# ADC_board.net
KiCad netlist of a schematic drawn in Altium Designer
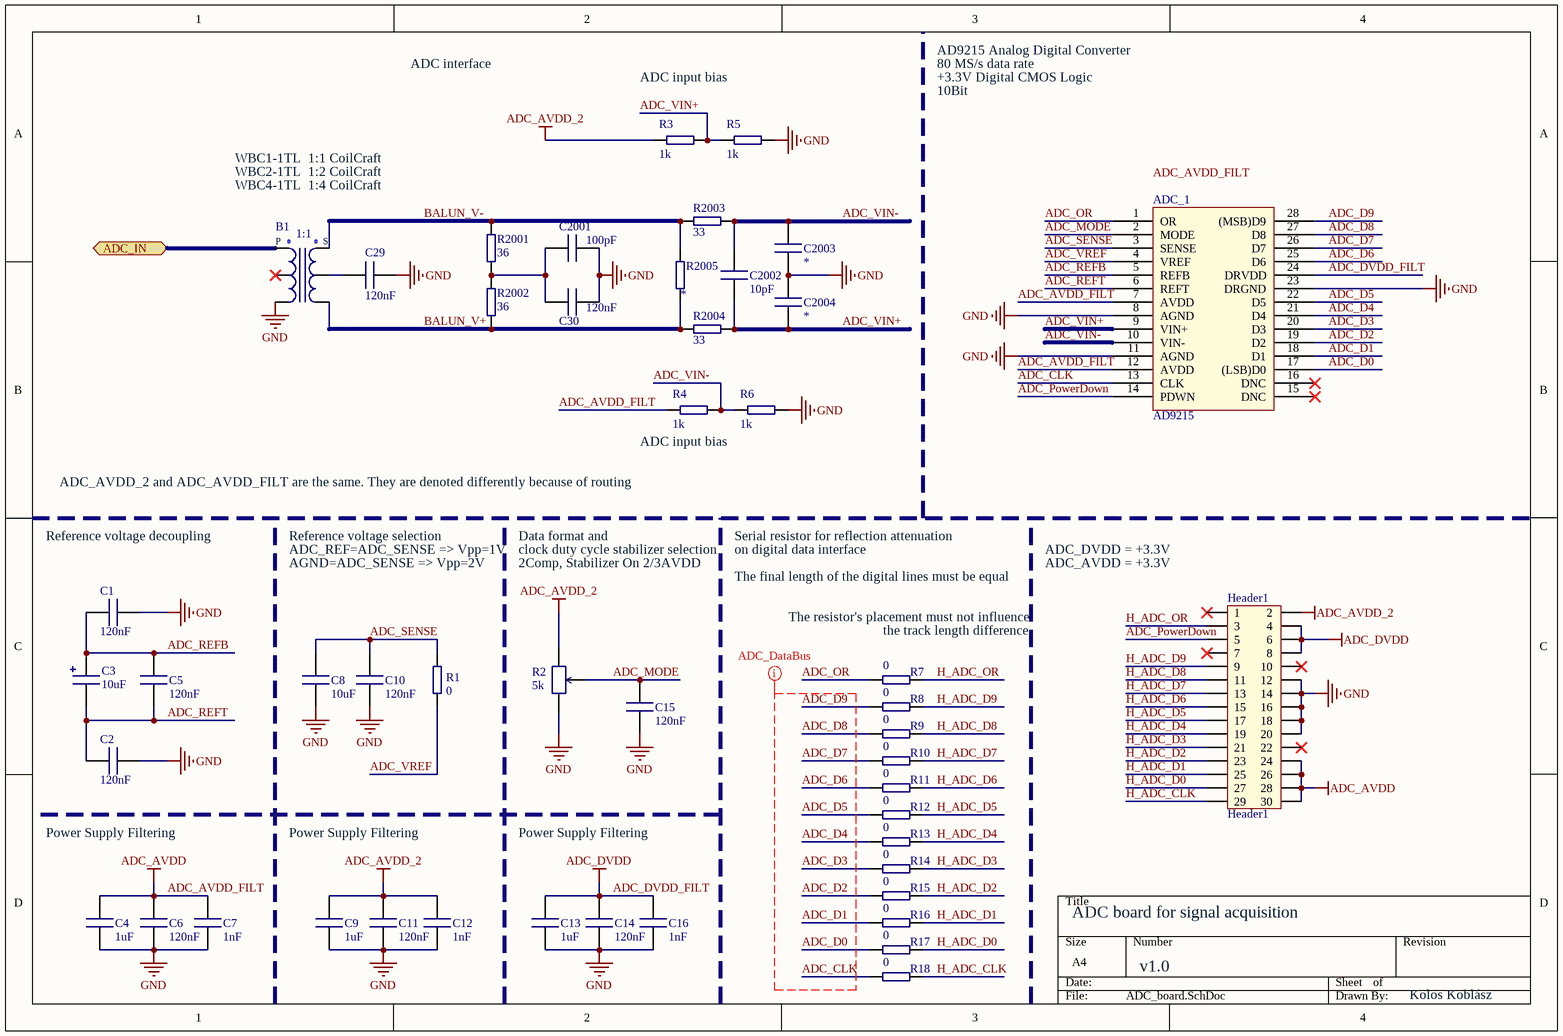
[diagram p0: ADC_board.SchDoc]

(export (version "E")
  (design (tool "Eeschema 10.0.6"))
  (components
    (comp (ref "ADC_1")
      (value "AD9215")
      (footprint "AD9215")
      (description "Analog Digital Converter")
      (fields (field (name "MANUFACTURER") "Analog Devices"))
      (libsource (lib "RadioProjectSchLib") (part "AD9215"))
    )
    (comp (ref "B1")
      (value "Balun")
      (footprint "Balun_Coil_Craft_WBC")
      (description "SMD Balun")
      (fields
        (field (name "IMPEDANCETRANSFORMATION P : S") "1:1")
        (field (name "MANUFACTURER") "CoilCraft")
        (field (name "PARTNUMBER") "WBC1-1TL")
      )
      (libsource (lib "RadioProjectSchLib") (part "Balun3"))
    )
    (comp (ref "C1")
      (value "120nF")
      (footprint "0805 SMD Passive")
      (description "SMD Capacitor")
      (fields (field (name "Comment") "Cap1"))
      (libsource (lib "RadioProjectSchLib") (part "Cap1"))
    )
    (comp (ref "C2")
      (value "120nF")
      (footprint "0805 SMD Passive")
      (description "SMD Capacitor")
      (fields (field (name "Comment") "Cap1"))
      (libsource (lib "RadioProjectSchLib") (part "Cap1"))
    )
    (comp (ref "C3")
      (value "10uF")
      (footprint "ELKO_CAP")
      (description "SMD Polarized Capacitor")
      (fields (field (name "Comment") "Cap2"))
      (libsource (lib "RadioProjectSchLib") (part "Cap2"))
    )
    (comp (ref "C4")
      (value "1uF")
      (footprint "0805 SMD Passive")
      (description "SMD Capacitor")
      (fields (field (name "Comment") "Cap1"))
      (libsource (lib "RadioProjectSchLib") (part "Cap1"))
    )
    (comp (ref "C5")
      (value "120nF")
      (footprint "0805 SMD Passive")
      (description "SMD Capacitor")
      (fields (field (name "Comment") "Cap1"))
      (libsource (lib "RadioProjectSchLib") (part "Cap1"))
    )
    (comp (ref "C6")
      (value "120nF")
      (footprint "0805 SMD Passive")
      (description "SMD Capacitor")
      (fields (field (name "Comment") "Cap1"))
      (libsource (lib "RadioProjectSchLib") (part "Cap1"))
    )
    (comp (ref "C7")
      (value "1nF")
      (footprint "0805 SMD Passive")
      (description "SMD Capacitor")
      (fields (field (name "Comment") "Cap1"))
      (libsource (lib "RadioProjectSchLib") (part "Cap1"))
    )
    (comp (ref "C8")
      (value "10uF")
      (footprint "0805 SMD Passive")
      (description "SMD Capacitor")
      (fields (field (name "Comment") "Cap1"))
      (libsource (lib "RadioProjectSchLib") (part "Cap1"))
    )
    (comp (ref "C9")
      (value "1uF")
      (footprint "0805 SMD Passive")
      (description "SMD Capacitor")
      (fields (field (name "Comment") "Cap1"))
      (libsource (lib "RadioProjectSchLib") (part "Cap1"))
    )
    (comp (ref "C10")
      (value "120nF")
      (footprint "0805 SMD Passive")
      (description "SMD Capacitor")
      (fields (field (name "Comment") "Cap1"))
      (libsource (lib "RadioProjectSchLib") (part "Cap1"))
    )
    (comp (ref "C11")
      (value "120nF")
      (footprint "0805 SMD Passive")
      (description "SMD Capacitor")
      (fields (field (name "Comment") "Cap1"))
      (libsource (lib "RadioProjectSchLib") (part "Cap1"))
    )
    (comp (ref "C12")
      (value "1nF")
      (footprint "0805 SMD Passive")
      (description "SMD Capacitor")
      (fields (field (name "Comment") "Cap1"))
      (libsource (lib "RadioProjectSchLib") (part "Cap1"))
    )
    (comp (ref "C13")
      (value "1uF")
      (footprint "0805 SMD Passive")
      (description "SMD Capacitor")
      (fields (field (name "Comment") "Cap1"))
      (libsource (lib "RadioProjectSchLib") (part "Cap1"))
    )
    (comp (ref "C14")
      (value "120nF")
      (footprint "0805 SMD Passive")
      (description "SMD Capacitor")
      (fields (field (name "Comment") "Cap1"))
      (libsource (lib "RadioProjectSchLib") (part "Cap1"))
    )
    (comp (ref "C15")
      (value "120nF")
      (footprint "0805 SMD Passive")
      (description "SMD Capacitor")
      (fields (field (name "Comment") "Cap1"))
      (libsource (lib "RadioProjectSchLib") (part "Cap1"))
    )
    (comp (ref "C16")
      (value "1nF")
      (footprint "0805 SMD Passive")
      (description "SMD Capacitor")
      (fields (field (name "Comment") "Cap1"))
      (libsource (lib "RadioProjectSchLib") (part "Cap1"))
    )
    (comp (ref "C29")
      (value "120nF")
      (footprint "0805 SMD Passive")
      (description "SMD Capacitor")
      (fields (field (name "Comment") "Cap1"))
      (libsource (lib "RadioProjectSchLib") (part "Cap1"))
    )
    (comp (ref "C30")
      (value "120nF")
      (footprint "0805 SMD Passive")
      (description "SMD Capacitor")
      (fields (field (name "Comment") "Cap1"))
      (libsource (lib "RadioProjectSchLib") (part "Cap1"))
    )
    (comp (ref "C2001")
      (value "100pF")
      (footprint "0805 SMD Passive")
      (description "SMD Capacitor")
      (fields (field (name "Comment") "Cap1"))
      (libsource (lib "RadioProjectSchLib") (part "Cap1"))
    )
    (comp (ref "C2002")
      (value "10pF")
      (footprint "0805 SMD Passive")
      (description "SMD Capacitor")
      (fields (field (name "Comment") "Cap1"))
      (libsource (lib "RadioProjectSchLib") (part "Cap1"))
    )
    (comp (ref "C2003")
      (value "Cap1")
      (footprint "0805 SMD Passive")
      (description "SMD Capacitor")
      (fields (field (name "ALTIUM_VALUE") "*"))
      (libsource (lib "RadioProjectSchLib") (part "Cap1"))
    )
    (comp (ref "C2004")
      (value "Cap1")
      (footprint "0805 SMD Passive")
      (description "SMD Capacitor")
      (fields (field (name "ALTIUM_VALUE") "*"))
      (libsource (lib "RadioProjectSchLib") (part "Cap1"))
    )
    (comp (ref "Header1")
      (value "Header1")
      (footprint "Header1")
      (description "29 Pin Header")
      (fields (field (name "PARTNUMBER") "TLW-115-01-G-D-002-RA"))
      (libsource (lib "RadioProjectSchLib") (part "Header1"))
    )
    (comp (ref "R1")
      (value "0")
      (footprint "0805 SMD Passive")
      (description "SMD Resistor")
      (fields (field (name "Comment") "Resistor"))
      (libsource (lib "RadioProjectSchLib") (part "Res1"))
    )
    (comp (ref "R2")
      (value "5k")
      (footprint "TC33-2")
      (description "SMD Variable Resistor")
      (fields (field (name "Comment") "VariableResistor"))
      (libsource (lib "RadioProjectSchLib") (part "VarRes1"))
    )
    (comp (ref "R3")
      (value "1k")
      (footprint "0805 SMD Passive")
      (description "SMD Resistor")
      (fields (field (name "Comment") "Resistor"))
      (libsource (lib "RadioProjectSchLib") (part "Res1"))
    )
    (comp (ref "R4")
      (value "1k")
      (footprint "0805 SMD Passive")
      (description "SMD Resistor")
      (fields (field (name "Comment") "Resistor"))
      (libsource (lib "RadioProjectSchLib") (part "Res1"))
    )
    (comp (ref "R5")
      (value "1k")
      (footprint "0805 SMD Passive")
      (description "SMD Resistor")
      (fields (field (name "Comment") "Resistor"))
      (libsource (lib "RadioProjectSchLib") (part "Res1"))
    )
    (comp (ref "R6")
      (value "1k")
      (footprint "0805 SMD Passive")
      (description "SMD Resistor")
      (fields (field (name "Comment") "Resistor"))
      (libsource (lib "RadioProjectSchLib") (part "Res1"))
    )
    (comp (ref "R7")
      (value "0")
      (footprint "0805 SMD Passive")
      (description "SMD Resistor")
      (fields (field (name "Comment") "Resistor"))
      (libsource (lib "RadioProjectSchLib") (part "Res1"))
    )
    (comp (ref "R8")
      (value "0")
      (footprint "0805 SMD Passive")
      (description "SMD Resistor")
      (fields (field (name "Comment") "Resistor"))
      (libsource (lib "RadioProjectSchLib") (part "Res1"))
    )
    (comp (ref "R9")
      (value "0")
      (footprint "0805 SMD Passive")
      (description "SMD Resistor")
      (fields (field (name "Comment") "Resistor"))
      (libsource (lib "RadioProjectSchLib") (part "Res1"))
    )
    (comp (ref "R10")
      (value "0")
      (footprint "0805 SMD Passive")
      (description "SMD Resistor")
      (fields (field (name "Comment") "Resistor"))
      (libsource (lib "RadioProjectSchLib") (part "Res1"))
    )
    (comp (ref "R11")
      (value "0")
      (footprint "0805 SMD Passive")
      (description "SMD Resistor")
      (fields (field (name "Comment") "Resistor"))
      (libsource (lib "RadioProjectSchLib") (part "Res1"))
    )
    (comp (ref "R12")
      (value "0")
      (footprint "0805 SMD Passive")
      (description "SMD Resistor")
      (fields (field (name "Comment") "Resistor"))
      (libsource (lib "RadioProjectSchLib") (part "Res1"))
    )
    (comp (ref "R13")
      (value "0")
      (footprint "0805 SMD Passive")
      (description "SMD Resistor")
      (fields (field (name "Comment") "Resistor"))
      (libsource (lib "RadioProjectSchLib") (part "Res1"))
    )
    (comp (ref "R14")
      (value "0")
      (footprint "0805 SMD Passive")
      (description "SMD Resistor")
      (fields (field (name "Comment") "Resistor"))
      (libsource (lib "RadioProjectSchLib") (part "Res1"))
    )
    (comp (ref "R15")
      (value "0")
      (footprint "0805 SMD Passive")
      (description "SMD Resistor")
      (fields (field (name "Comment") "Resistor"))
      (libsource (lib "RadioProjectSchLib") (part "Res1"))
    )
    (comp (ref "R16")
      (value "0")
      (footprint "0805 SMD Passive")
      (description "SMD Resistor")
      (fields (field (name "Comment") "Resistor"))
      (libsource (lib "RadioProjectSchLib") (part "Res1"))
    )
    (comp (ref "R17")
      (value "0")
      (footprint "0805 SMD Passive")
      (description "SMD Resistor")
      (fields (field (name "Comment") "Resistor"))
      (libsource (lib "RadioProjectSchLib") (part "Res1"))
    )
    (comp (ref "R18")
      (value "0")
      (footprint "0805 SMD Passive")
      (description "SMD Resistor")
      (fields (field (name "Comment") "Resistor"))
      (libsource (lib "RadioProjectSchLib") (part "Res1"))
    )
    (comp (ref "R2001")
      (value "36")
      (footprint "0805 SMD Passive")
      (description "SMD Resistor")
      (fields (field (name "Comment") "Resistor"))
      (libsource (lib "RadioProjectSchLib") (part "Res1"))
    )
    (comp (ref "R2002")
      (value "36")
      (footprint "0805 SMD Passive")
      (description "SMD Resistor")
      (fields (field (name "Comment") "Resistor"))
      (libsource (lib "RadioProjectSchLib") (part "Res1"))
    )
    (comp (ref "R2003")
      (value "33")
      (footprint "0805 SMD Passive")
      (description "SMD Resistor")
      (fields (field (name "Comment") "Resistor"))
      (libsource (lib "RadioProjectSchLib") (part "Res1"))
    )
    (comp (ref "R2004")
      (value "33")
      (footprint "0805 SMD Passive")
      (description "SMD Resistor")
      (fields (field (name "Comment") "Resistor"))
      (libsource (lib "RadioProjectSchLib") (part "Res1"))
    )
    (comp (ref "R2005")
      (value "Resistor")
      (footprint "0805 SMD Passive")
      (description "SMD Resistor")
      (fields (field (name "ALTIUM_VALUE") "*"))
      (libsource (lib "RadioProjectSchLib") (part "Res1"))
    )
  )
  (nets
    (net (code "1") (name "/ADC_CLK") (class "Default")
      (node (ref "ADC_1") (pin "13") (pinfunction "CLK_13") (pintype "passive"))
      (node (ref "R18") (pin "1") (pinfunction "*_1") (pintype "passive"))
    )
    (net (code "2") (name "/ADC_D0") (class "Default")
      (node (ref "ADC_1") (pin "17") (pinfunction "(LSB)D0_17") (pintype "passive"))
      (node (ref "R17") (pin "1") (pinfunction "*_1") (pintype "passive"))
    )
    (net (code "3") (name "/ADC_D1") (class "Default")
      (node (ref "ADC_1") (pin "18") (pinfunction "D1_18") (pintype "passive"))
      (node (ref "R16") (pin "1") (pinfunction "*_1") (pintype "passive"))
    )
    (net (code "4") (name "/ADC_D2") (class "Default")
      (node (ref "ADC_1") (pin "19") (pinfunction "D2_19") (pintype "passive"))
      (node (ref "R15") (pin "1") (pinfunction "*_1") (pintype "passive"))
    )
    (net (code "5") (name "/ADC_D3") (class "Default")
      (node (ref "ADC_1") (pin "20") (pinfunction "D3_20") (pintype "passive"))
      (node (ref "R14") (pin "1") (pinfunction "*_1") (pintype "passive"))
    )
    (net (code "6") (name "/ADC_D4") (class "Default")
      (node (ref "ADC_1") (pin "21") (pinfunction "D4_21") (pintype "passive"))
      (node (ref "R13") (pin "1") (pinfunction "*_1") (pintype "passive"))
    )
    (net (code "7") (name "/ADC_D5") (class "Default")
      (node (ref "ADC_1") (pin "22") (pinfunction "D5_22") (pintype "passive"))
      (node (ref "R12") (pin "1") (pinfunction "*_1") (pintype "passive"))
    )
    (net (code "8") (name "/ADC_D6") (class "Default")
      (node (ref "ADC_1") (pin "25") (pinfunction "D6_25") (pintype "passive"))
      (node (ref "R11") (pin "1") (pinfunction "*_1") (pintype "passive"))
    )
    (net (code "9") (name "/ADC_D7") (class "Default")
      (node (ref "ADC_1") (pin "26") (pinfunction "D7_26") (pintype "passive"))
      (node (ref "R10") (pin "1") (pinfunction "*_1") (pintype "passive"))
    )
    (net (code "10") (name "/ADC_D8") (class "Default")
      (node (ref "ADC_1") (pin "27") (pinfunction "D8_27") (pintype "passive"))
      (node (ref "R9") (pin "1") (pinfunction "*_1") (pintype "passive"))
    )
    (net (code "11") (name "/ADC_D9") (class "Default")
      (node (ref "ADC_1") (pin "28") (pinfunction "(MSB)D9_28") (pintype "passive"))
      (node (ref "R8") (pin "1") (pinfunction "*_1") (pintype "passive"))
    )
    (net (code "12") (name "/ADC_IN") (class "Default")
      (node (ref "B1") (pin "6") (pinfunction "6_6") (pintype "passive"))
    )
    (net (code "13") (name "/ADC_MODE") (class "Default")
      (node (ref "ADC_1") (pin "2") (pinfunction "MODE_2") (pintype "passive"))
      (node (ref "C15") (pin "1") (pinfunction "*_1") (pintype "passive"))
      (node (ref "R2") (pin "3") (pinfunction "3_3") (pintype "passive"))
    )
    (net (code "14") (name "/ADC_OR") (class "Default")
      (node (ref "ADC_1") (pin "1") (pinfunction "OR_1") (pintype "passive"))
      (node (ref "R7") (pin "1") (pinfunction "*_1") (pintype "passive"))
    )
    (net (code "15") (name "/ADC_PowerDown") (class "Default")
      (node (ref "ADC_1") (pin "14") (pinfunction "PDWN_14") (pintype "passive"))
      (node (ref "Header1") (pin "5") (pinfunction "5_5") (pintype "passive"))
    )
    (net (code "16") (name "/ADC_REFB") (class "Default")
      (node (ref "ADC_1") (pin "5") (pinfunction "REFB_5") (pintype "passive"))
      (node (ref "C1") (pin "2") (pinfunction "*_2") (pintype "passive"))
      (node (ref "C3") (pin "1") (pinfunction "*_1") (pintype "passive"))
      (node (ref "C5") (pin "1") (pinfunction "*_1") (pintype "passive"))
    )
    (net (code "17") (name "/ADC_REFT") (class "Default")
      (node (ref "ADC_1") (pin "6") (pinfunction "REFT_6") (pintype "passive"))
      (node (ref "C2") (pin "1") (pinfunction "*_1") (pintype "passive"))
      (node (ref "C3") (pin "2") (pinfunction "*_2") (pintype "passive"))
      (node (ref "C5") (pin "2") (pinfunction "*_2") (pintype "passive"))
    )
    (net (code "18") (name "/ADC_SENSE") (class "Default")
      (node (ref "ADC_1") (pin "3") (pinfunction "SENSE_3") (pintype "passive"))
      (node (ref "C10") (pin "1") (pinfunction "*_1") (pintype "passive"))
      (node (ref "C8") (pin "1") (pinfunction "*_1") (pintype "passive"))
      (node (ref "R1") (pin "2") (pinfunction "*_2") (pintype "passive"))
    )
    (net (code "19") (name "/ADC_VIN+") (class "Default")
      (node (ref "ADC_1") (pin "9") (pinfunction "VIN+_9") (pintype "passive"))
      (node (ref "C2002") (pin "2") (pinfunction "*_2") (pintype "passive"))
      (node (ref "C2004") (pin "2") (pinfunction "*_2") (pintype "passive"))
      (node (ref "R2004") (pin "2") (pinfunction "*_2") (pintype "passive"))
      (node (ref "R3") (pin "2") (pinfunction "*_2") (pintype "passive"))
      (node (ref "R5") (pin "1") (pinfunction "*_1") (pintype "passive"))
    )
    (net (code "20") (name "/ADC_VIN-") (class "Default")
      (node (ref "ADC_1") (pin "10") (pinfunction "VIN-_10") (pintype "passive"))
      (node (ref "C2002") (pin "1") (pinfunction "*_1") (pintype "passive"))
      (node (ref "C2003") (pin "1") (pinfunction "*_1") (pintype "passive"))
      (node (ref "R2003") (pin "2") (pinfunction "*_2") (pintype "passive"))
      (node (ref "R4") (pin "2") (pinfunction "*_2") (pintype "passive"))
      (node (ref "R6") (pin "1") (pinfunction "*_1") (pintype "passive"))
    )
    (net (code "21") (name "/ADC_VREF") (class "Default")
      (node (ref "ADC_1") (pin "4") (pinfunction "VREF_4") (pintype "passive"))
      (node (ref "R1") (pin "1") (pinfunction "*_1") (pintype "passive"))
    )
    (net (code "22") (name "/BALUN_V+") (class "Default")
      (node (ref "B1") (pin "3") (pinfunction "3_3") (pintype "passive"))
      (node (ref "R2002") (pin "1") (pinfunction "*_1") (pintype "passive"))
      (node (ref "R2004") (pin "1") (pinfunction "*_1") (pintype "passive"))
      (node (ref "R2005") (pin "1") (pinfunction "*_1") (pintype "passive"))
    )
    (net (code "23") (name "/BALUN_V-") (class "Default")
      (node (ref "B1") (pin "1") (pinfunction "1_1") (pintype "passive"))
      (node (ref "R2001") (pin "2") (pinfunction "*_2") (pintype "passive"))
      (node (ref "R2003") (pin "1") (pinfunction "*_1") (pintype "passive"))
      (node (ref "R2005") (pin "2") (pinfunction "*_2") (pintype "passive"))
    )
    (net (code "24") (name "/H_ADC_CLK") (class "Default")
      (node (ref "Header1") (pin "29") (pinfunction "29_29") (pintype "passive"))
      (node (ref "R18") (pin "2") (pinfunction "*_2") (pintype "passive"))
    )
    (net (code "25") (name "/H_ADC_D0") (class "Default")
      (node (ref "Header1") (pin "27") (pinfunction "27_27") (pintype "passive"))
      (node (ref "R17") (pin "2") (pinfunction "*_2") (pintype "passive"))
    )
    (net (code "26") (name "/H_ADC_D1") (class "Default")
      (node (ref "Header1") (pin "25") (pinfunction "25_25") (pintype "passive"))
      (node (ref "R16") (pin "2") (pinfunction "*_2") (pintype "passive"))
    )
    (net (code "27") (name "/H_ADC_D2") (class "Default")
      (node (ref "Header1") (pin "23") (pinfunction "23_23") (pintype "passive"))
      (node (ref "R15") (pin "2") (pinfunction "*_2") (pintype "passive"))
    )
    (net (code "28") (name "/H_ADC_D3") (class "Default")
      (node (ref "Header1") (pin "21") (pinfunction "21_21") (pintype "passive"))
      (node (ref "R14") (pin "2") (pinfunction "*_2") (pintype "passive"))
    )
    (net (code "29") (name "/H_ADC_D4") (class "Default")
      (node (ref "Header1") (pin "19") (pinfunction "19_19") (pintype "passive"))
      (node (ref "R13") (pin "2") (pinfunction "*_2") (pintype "passive"))
    )
    (net (code "30") (name "/H_ADC_D5") (class "Default")
      (node (ref "Header1") (pin "17") (pinfunction "17_17") (pintype "passive"))
      (node (ref "R12") (pin "2") (pinfunction "*_2") (pintype "passive"))
    )
    (net (code "31") (name "/H_ADC_D6") (class "Default")
      (node (ref "Header1") (pin "15") (pinfunction "15_15") (pintype "passive"))
      (node (ref "R11") (pin "2") (pinfunction "*_2") (pintype "passive"))
    )
    (net (code "32") (name "/H_ADC_D7") (class "Default")
      (node (ref "Header1") (pin "13") (pinfunction "13_13") (pintype "passive"))
      (node (ref "R10") (pin "2") (pinfunction "*_2") (pintype "passive"))
    )
    (net (code "33") (name "/H_ADC_D8") (class "Default")
      (node (ref "Header1") (pin "11") (pinfunction "11_11") (pintype "passive"))
      (node (ref "R9") (pin "2") (pinfunction "*_2") (pintype "passive"))
    )
    (net (code "34") (name "/H_ADC_D9") (class "Default")
      (node (ref "Header1") (pin "9") (pinfunction "9_9") (pintype "passive"))
      (node (ref "R8") (pin "2") (pinfunction "*_2") (pintype "passive"))
    )
    (net (code "35") (name "/H_ADC_OR") (class "Default")
      (node (ref "Header1") (pin "3") (pinfunction "3_3") (pintype "passive"))
      (node (ref "R7") (pin "2") (pinfunction "*_2") (pintype "passive"))
    )
    (net (code "36") (name "ADC_AVDD") (class "Default")
      (node (ref "ADC_1") (pin "12") (pinfunction "AVDD_12") (pintype "passive"))
      (node (ref "ADC_1") (pin "7") (pinfunction "AVDD_7") (pintype "passive"))
      (node (ref "C4") (pin "1") (pinfunction "*_1") (pintype "passive"))
      (node (ref "C6") (pin "1") (pinfunction "*_1") (pintype "passive"))
      (node (ref "C7") (pin "1") (pinfunction "*_1") (pintype "passive"))
      (node (ref "Header1") (pin "24") (pinfunction "24_24") (pintype "passive"))
      (node (ref "Header1") (pin "26") (pinfunction "26_26") (pintype "passive"))
      (node (ref "Header1") (pin "28") (pinfunction "28_28") (pintype "passive"))
      (node (ref "Header1") (pin "30") (pinfunction "30_30") (pintype "passive"))
      (node (ref "R4") (pin "1") (pinfunction "*_1") (pintype "passive"))
    )
    (net (code "37") (name "ADC_AVDD_2") (class "Default")
      (node (ref "C11") (pin "1") (pinfunction "*_1") (pintype "passive"))
      (node (ref "C12") (pin "1") (pinfunction "*_1") (pintype "passive"))
      (node (ref "C9") (pin "1") (pinfunction "*_1") (pintype "passive"))
      (node (ref "Header1") (pin "2") (pinfunction "2_2") (pintype "passive"))
      (node (ref "R2") (pin "1") (pinfunction "*_1") (pintype "passive"))
      (node (ref "R3") (pin "1") (pinfunction "*_1") (pintype "passive"))
    )
    (net (code "38") (name "ADC_DVDD") (class "Default")
      (node (ref "ADC_1") (pin "24") (pinfunction "DRVDD_24") (pintype "passive"))
      (node (ref "C13") (pin "1") (pinfunction "*_1") (pintype "passive"))
      (node (ref "C14") (pin "1") (pinfunction "*_1") (pintype "passive"))
      (node (ref "C16") (pin "1") (pinfunction "*_1") (pintype "passive"))
      (node (ref "Header1") (pin "4") (pinfunction "4_4") (pintype "passive"))
      (node (ref "Header1") (pin "6") (pinfunction "6_6") (pintype "passive"))
      (node (ref "Header1") (pin "8") (pinfunction "8_8") (pintype "passive"))
    )
    (net (code "39") (name "GND") (class "Default")
      (node (ref "ADC_1") (pin "11") (pinfunction "AGND_11") (pintype "passive"))
      (node (ref "ADC_1") (pin "23") (pinfunction "DRGND_23") (pintype "passive"))
      (node (ref "ADC_1") (pin "8") (pinfunction "AGND_8") (pintype "passive"))
      (node (ref "B1") (pin "4") (pinfunction "4_4") (pintype "passive"))
      (node (ref "C1") (pin "1") (pinfunction "*_1") (pintype "passive"))
      (node (ref "C10") (pin "2") (pinfunction "*_2") (pintype "passive"))
      (node (ref "C11") (pin "2") (pinfunction "*_2") (pintype "passive"))
      (node (ref "C12") (pin "2") (pinfunction "*_2") (pintype "passive"))
      (node (ref "C13") (pin "2") (pinfunction "*_2") (pintype "passive"))
      (node (ref "C14") (pin "2") (pinfunction "*_2") (pintype "passive"))
      (node (ref "C15") (pin "2") (pinfunction "*_2") (pintype "passive"))
      (node (ref "C16") (pin "2") (pinfunction "*_2") (pintype "passive"))
      (node (ref "C2") (pin "2") (pinfunction "*_2") (pintype "passive"))
      (node (ref "C2001") (pin "1") (pinfunction "*_1") (pintype "passive"))
      (node (ref "C2003") (pin "2") (pinfunction "*_2") (pintype "passive"))
      (node (ref "C2004") (pin "1") (pinfunction "*_1") (pintype "passive"))
      (node (ref "C29") (pin "1") (pinfunction "*_1") (pintype "passive"))
      (node (ref "C30") (pin "1") (pinfunction "*_1") (pintype "passive"))
      (node (ref "C4") (pin "2") (pinfunction "*_2") (pintype "passive"))
      (node (ref "C6") (pin "2") (pinfunction "*_2") (pintype "passive"))
      (node (ref "C7") (pin "2") (pinfunction "*_2") (pintype "passive"))
      (node (ref "C8") (pin "2") (pinfunction "*_2") (pintype "passive"))
      (node (ref "C9") (pin "2") (pinfunction "*_2") (pintype "passive"))
      (node (ref "Header1") (pin "12") (pinfunction "12_12") (pintype "passive"))
      (node (ref "Header1") (pin "14") (pinfunction "14_14") (pintype "passive"))
      (node (ref "Header1") (pin "16") (pinfunction "16_16") (pintype "passive"))
      (node (ref "Header1") (pin "18") (pinfunction "18_18") (pintype "passive"))
      (node (ref "Header1") (pin "20") (pinfunction "20_20") (pintype "passive"))
      (node (ref "R2") (pin "2") (pinfunction "*_2") (pintype "passive"))
      (node (ref "R5") (pin "2") (pinfunction "*_2") (pintype "passive"))
      (node (ref "R6") (pin "2") (pinfunction "*_2") (pintype "passive"))
    )
    (net (code "40") (name "Net-(B1-Pad2)") (class "Default")
      (node (ref "B1") (pin "2") (pinfunction "2_2") (pintype "passive"))
      (node (ref "C29") (pin "2") (pinfunction "*_2") (pintype "passive"))
    )
    (net (code "41") (name "Net-(C2001-*-Pad2)") (class "Default")
      (node (ref "C2001") (pin "2") (pinfunction "*_2") (pintype "passive"))
      (node (ref "C30") (pin "2") (pinfunction "*_2") (pintype "passive"))
      (node (ref "R2001") (pin "1") (pinfunction "*_1") (pintype "passive"))
      (node (ref "R2002") (pin "2") (pinfunction "*_2") (pintype "passive"))
    )
    (net (code "42") (name "unconnected-(ADC_1-DNC-Pad15)") (class "Default")
      (node (ref "ADC_1") (pin "15") (pinfunction "DNC_15") (pintype "passive+no_connect"))
    )
    (net (code "43") (name "unconnected-(ADC_1-DNC-Pad16)") (class "Default")
      (node (ref "ADC_1") (pin "16") (pinfunction "DNC_16") (pintype "passive+no_connect"))
    )
    (net (code "44") (name "unconnected-(B1-Pad5)") (class "Default")
      (node (ref "B1") (pin "5") (pinfunction "5_5") (pintype "passive+no_connect"))
    )
    (net (code "45") (name "unconnected-(Header1-Pad1)") (class "Default")
      (node (ref "Header1") (pin "1") (pinfunction "1_1") (pintype "passive+no_connect"))
    )
    (net (code "46") (name "unconnected-(Header1-Pad7)") (class "Default")
      (node (ref "Header1") (pin "7") (pinfunction "7_7") (pintype "passive+no_connect"))
    )
    (net (code "47") (name "unconnected-(Header1-Pad10)") (class "Default")
      (node (ref "Header1") (pin "10") (pinfunction "10_10") (pintype "passive+no_connect"))
    )
    (net (code "48") (name "unconnected-(Header1-Pad22)") (class "Default")
      (node (ref "Header1") (pin "22") (pinfunction "22_22") (pintype "passive+no_connect"))
    )
  )
)
